# authenticator_breakout.net
KiCad netlist of a schematic drawn in EAGLE
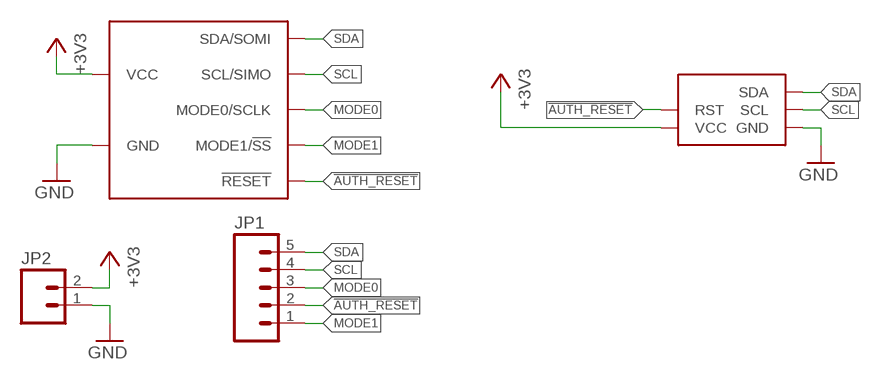
[diagram p0: schematic, sheet 1]

(export (version "E")
  (design (tool "Eeschema 10.0.6"))
  (components
    (comp (ref "JP1")
      (value "M05LOCK")
      (footprint "eagle-import:1X05_LOCK")
      (libsource (lib "eagle-import") (part "M05LOCK"))
    )
    (comp (ref "JP2")
      (value "M02LOCK")
      (footprint "eagle-import:1X02_LOCK")
      (libsource (lib "eagle-import") (part "M02LOCK"))
    )
    (comp (ref "U$2")
      (value "AUTHENTICATORQFN")
      (footprint "eagle-import:AUTH_QFN20")
      (libsource (lib "eagle-import") (part "AUTHENTICATORQFN"))
    )
    (comp (ref "U$4")
      (value "AUTHENTICATOR_2C")
      (footprint "eagle-import:AUTH_SQC")
      (libsource (lib "eagle-import") (part "AUTHENTICATOR_2C"))
    )
  )
  (nets
    (net (code "1") (name "+3V3") (class "Default")
      (node (ref "JP2") (pin "2") (pinfunction "2_2") (pintype "passive"))
      (node (ref "U$2") (pin "P$5") (pinfunction "VCC_P$5") (pintype "bidirectional"))
      (node (ref "U$4") (pin "P$8") (pinfunction "VCC_P$8") (pintype "bidirectional"))
    )
    (net (code "2") (name "/~{AUTH_RESET}") (class "Default")
      (node (ref "JP1") (pin "2") (pinfunction "2_2") (pintype "passive"))
      (node (ref "U$2") (pin "P$4") (pinfunction "~{RESET}_P$4") (pintype "bidirectional"))
      (node (ref "U$4") (pin "P$7") (pinfunction "RST_P$7") (pintype "bidirectional"))
    )
    (net (code "3") (name "GND") (class "Default")
      (node (ref "JP2") (pin "1") (pinfunction "1_1") (pintype "passive"))
      (node (ref "U$2") (pin "P$11") (pinfunction "GND_P$11") (pintype "bidirectional"))
      (node (ref "U$4") (pin "P$1") (pinfunction "GND_P$1") (pintype "bidirectional"))
    )
    (net (code "4") (name "MODE0") (class "Default")
      (node (ref "JP1") (pin "3") (pinfunction "3_3") (pintype "passive"))
      (node (ref "U$2") (pin "P$14") (pinfunction "MODE0/SCLK_P$14") (pintype "bidirectional"))
    )
    (net (code "5") (name "MODE1") (class "Default")
      (node (ref "JP1") (pin "1") (pinfunction "1_1") (pintype "passive"))
      (node (ref "U$2") (pin "P$2") (pinfunction "MODE1/~{SS}_P$2") (pintype "bidirectional"))
    )
    (net (code "6") (name "SCL") (class "Default")
      (node (ref "JP1") (pin "4") (pinfunction "4_4") (pintype "passive"))
      (node (ref "U$2") (pin "P$12") (pinfunction "SCL/SIMO_P$12") (pintype "bidirectional"))
      (node (ref "U$4") (pin "P$6") (pinfunction "SCL_P$6") (pintype "bidirectional"))
    )
    (net (code "7") (name "SDA") (class "Default")
      (node (ref "JP1") (pin "5") (pinfunction "5_5") (pintype "passive"))
      (node (ref "U$2") (pin "P$13") (pinfunction "SDA/SOMI_P$13") (pintype "bidirectional"))
      (node (ref "U$4") (pin "P$2") (pinfunction "SDA_P$2") (pintype "bidirectional"))
    )
  )
)
